# ESC.net
KiCad netlist of a schematic drawn in Altium Designer
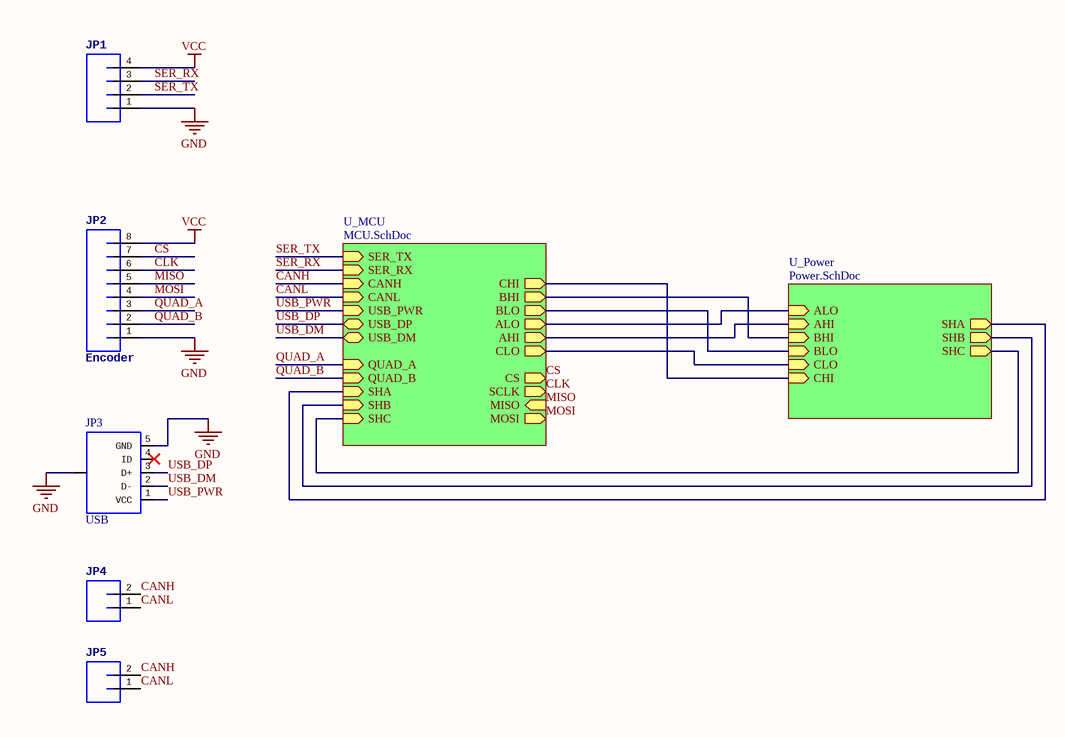
[diagram p0: ESC.SchDoc]

(export (version "E")
  (design (tool "Eeschema 10.0.6"))
  (components
    (comp (ref "JP1")
      (value "~")
      (footprint "JST-4-PTH-VERT")
      (libsource (lib "Components") (part "JST_4_VERT"))
    )
    (comp (ref "JP2")
      (value "Encoder")
      (footprint "JST-8-PTH-VERT")
      (libsource (lib "Components") (part "JST_8_VERT"))
    )
    (comp (ref "JP3")
      (value "USB")
      (footprint "USB-MICROB")
      (libsource (lib "Components") (part "USB_MICROB_PLUG-SMT"))
    )
    (comp (ref "JP4")
      (value "~")
      (footprint "JST-2-PTH-VERT")
      (libsource (lib "Components") (part "JST_2_VERT"))
    )
    (comp (ref "JP5")
      (value "~")
      (footprint "JST-2-PTH-VERT")
      (libsource (lib "Components") (part "JST_2_VERT"))
    )
  )
  (nets
    (net (code "5") (name "/CANH") (class "Default")
      (node (ref "JP4") (pin "2") (pinfunction "2_2") (pintype "passive"))
      (node (ref "JP5") (pin "2") (pinfunction "2_2") (pintype "passive"))
    )
    (net (code "6") (name "/CANL") (class "Default")
      (node (ref "JP4") (pin "1") (pinfunction "1_1") (pintype "passive"))
      (node (ref "JP5") (pin "1") (pinfunction "1_1") (pintype "passive"))
    )
    (net (code "8") (name "/CLK") (class "Default")
      (node (ref "JP2") (pin "6") (pinfunction "6_6") (pintype "passive"))
    )
    (net (code "10") (name "/CS") (class "Default")
      (node (ref "JP2") (pin "7") (pinfunction "7_7") (pintype "passive"))
    )
    (net (code "11") (name "/MISO") (class "Default")
      (node (ref "JP2") (pin "5") (pinfunction "5_5") (pintype "passive"))
    )
    (net (code "12") (name "/MOSI") (class "Default")
      (node (ref "JP2") (pin "4") (pinfunction "4_4") (pintype "passive"))
    )
    (net (code "13") (name "/QUAD_A") (class "Default")
      (node (ref "JP2") (pin "3") (pinfunction "3_3") (pintype "passive"))
    )
    (net (code "14") (name "/QUAD_B") (class "Default")
      (node (ref "JP2") (pin "2") (pinfunction "2_2") (pintype "passive"))
    )
    (net (code "15") (name "/SER_RX") (class "Default")
      (node (ref "JP1") (pin "3") (pinfunction "3_3") (pintype "passive"))
    )
    (net (code "16") (name "/SER_TX") (class "Default")
      (node (ref "JP1") (pin "2") (pinfunction "2_2") (pintype "passive"))
    )
    (net (code "20") (name "/USB_DM") (class "Default")
      (node (ref "JP3") (pin "2") (pinfunction "D-_2") (pintype "passive"))
    )
    (net (code "21") (name "/USB_DP") (class "Default")
      (node (ref "JP3") (pin "3") (pinfunction "D+_3") (pintype "passive"))
    )
    (net (code "22") (name "/USB_PWR") (class "Default")
      (node (ref "JP3") (pin "1") (pinfunction "VCC_1") (pintype "passive"))
    )
    (net (code "23") (name "GND") (class "Default")
      (node (ref "JP1") (pin "1") (pinfunction "1_1") (pintype "passive"))
      (node (ref "JP2") (pin "1") (pinfunction "1_1") (pintype "passive"))
      (node (ref "JP3") (pin "5") (pinfunction "GND_5") (pintype "passive"))
      (node (ref "JP3") (pin "6") (pinfunction "SHIELD_6") (pintype "passive"))
    )
    (net (code "24") (name "VCC") (class "Default")
      (node (ref "JP1") (pin "4") (pinfunction "4_4") (pintype "passive"))
      (node (ref "JP2") (pin "8") (pinfunction "8_8") (pintype "passive"))
    )
    (net (code "25") (name "unconnected-(JP3-ID-Pad4)") (class "Default")
      (node (ref "JP3") (pin "4") (pinfunction "ID_4") (pintype "passive+no_connect"))
    )
  )
)
